# V_AUX.net
KiCad netlist of a schematic drawn in Altium Designer
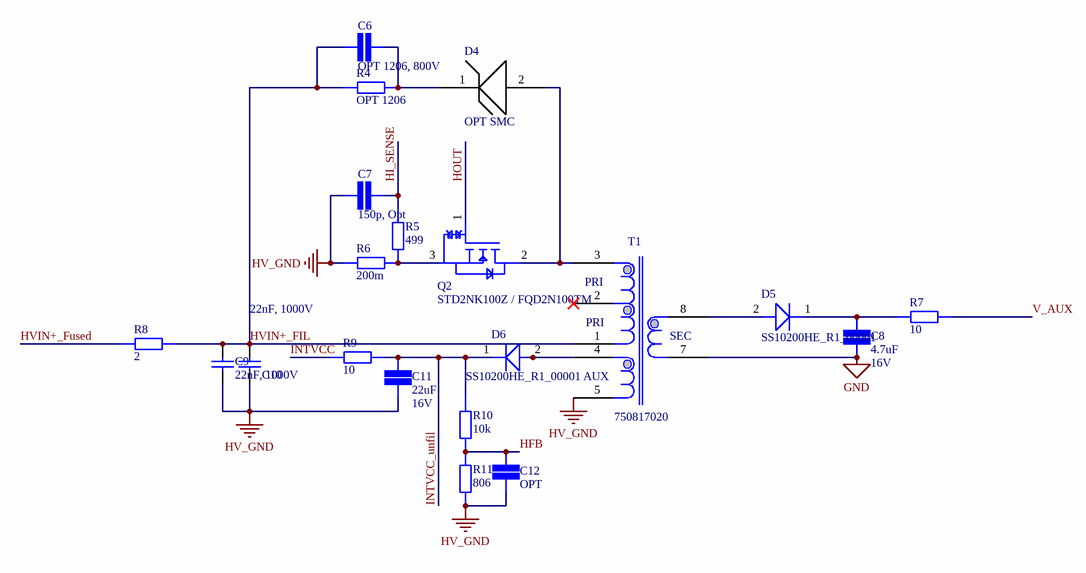
[diagram p0: V_AUX.SchDoc]

(export (version "E")
  (design (tool "Eeschema 10.0.6"))
  (components
    (comp (ref "C6")
      (value "OPT 1206, 800V")
      (footprint "CAP 1206/3216")
      (description "Capacitor with multiple Footprints")
      (fields (field (name "Comment") "SMD Capacitor"))
      (libsource (lib "") (part "SMD Capacitor_1"))
    )
    (comp (ref "C7")
      (value "150p, Opt")
      (footprint "CAP 0603/1608")
      (description "Capacitor with multiple Footprints")
      (fields (field (name "Comment") "SMD Capacitor"))
      (libsource (lib "") (part "SMD Capacitor_1"))
    )
    (comp (ref "C8")
      (value "4.7uF")
      (footprint "CAP 0603/1608")
      (description "Capacitor with multiple Footprints")
      (fields (field (name "VOLTAGE") "16V") (field (name "Comment") "SMD Capacitor"))
      (libsource (lib "Standardbauteile") (part "SMD Capacitor"))
    )
    (comp (ref "C9")
      (value "22nF, 1000V")
      (footprint "WCAP-CSMH_1210_H1.6")
      (description "WCAP-CSMH Multilayer Ceramic Chip Capacitor, size 1210, X7R Class II, 22nF, 1000V")
      (fields
        (field (name "MANUFACTURER PART NUMBER") "885342209007")
        (field (name "MANUFACTURER") "Wurth Elektronik")
      )
      (libsource (lib "Altium_WCAP-CSMH (rev20a)") (part "885342209007"))
    )
    (comp (ref "C10")
      (value "22nF, 1000V")
      (footprint "WCAP-CSMH_1210_H1.6")
      (description "WCAP-CSMH Multilayer Ceramic Chip Capacitor, size 1210, X7R Class II, 22nF, 1000V")
      (fields
        (field (name "MANUFACTURER PART NUMBER") "885342209007")
        (field (name "MANUFACTURER") "Wurth Elektronik")
      )
      (libsource (lib "Altium_WCAP-CSMH (rev20a)") (part "885342209007"))
    )
    (comp (ref "C11")
      (value "22uF")
      (footprint "CAP 0603/1608")
      (description "Capacitor with multiple Footprints")
      (fields (field (name "VOLTAGE") "16V") (field (name "Comment") "SMD Capacitor"))
      (libsource (lib "Standardbauteile") (part "SMD Capacitor"))
    )
    (comp (ref "C12")
      (value "OPT")
      (footprint "CAP 0603/1608")
      (description "Capacitor with multiple Footprints")
      (fields (field (name "Comment") "SMD Capacitor"))
      (libsource (lib "") (part "SMD Capacitor_2"))
    )
    (comp (ref "D4")
      (value "OPT SMC")
      (footprint "JEDEC DO-214AB")
      (fields
        (field (name "MANUFACTURER") "STMicroelectronics")
        (field (name "MANUFACTURER PART NUMBER") "SMC30J24A")
      )
      (libsource (lib "Integrated_LibraryLukas") (part "SMC30J24A"))
    )
    (comp (ref "D5")
      (value "SS10200HE_R1_00001")
      (footprint "Chip2PinSM127P600-8N")
      (description "Schottky 1A 200V SOD-123HE")
      (fields (field (name "MANUFACTURER") "Pan Jit"))
      (libsource (lib "Integrated_LibraryLukas_New") (part "SS10200HE_R1_00001"))
    )
    (comp (ref "D6")
      (value "SS10200HE_R1_00001")
      (footprint "Chip2PinSM127P600-8N")
      (description "Schottky 1A 200V SOD-123HE")
      (fields (field (name "MANUFACTURER") "Pan Jit"))
      (libsource (lib "Integrated_LibraryLukas_New") (part "SS10200HE_R1_00001"))
    )
    (comp (ref "Q2")
      (value "STD2NK100Z / FQD2N100TM")
      (footprint "DPAK TO-252")
      (description "N-channel 1000 V, 6.25 Ohm typ., 1.85 A, Zener-protected SuperMESH Power MOSFET in DPAK package")
      (fields
        (field (name "MANUFACTURER") "STMicroelectronics")
        (field (name "MANUFACTURER PART NUMBER") "STD2NK100Z")
      )
      (libsource (lib "Integrated_LibraryLukas_New") (part "STD2NK100Z"))
    )
    (comp (ref "R4")
      (value "OPT 1206")
      (footprint "STACKPOLE CSR1206")
      (description "Resistor with multiple footprints")
      (fields (field (name "Comment") "SMD Resistor"))
      (libsource (lib "Standardbauteile") (part "SMD Resistor"))
    )
    (comp (ref "R5")
      (value "499")
      (footprint "STACKPOLE CSR0603")
      (description "Resistor with multiple footprints")
      (fields (field (name "Comment") "SMD Resistor"))
      (libsource (lib "Standardbauteile") (part "SMD Resistor"))
    )
    (comp (ref "R6")
      (value "200m")
      (footprint "STACKPOLE CSR0603")
      (description "Resistor with multiple footprints")
      (fields (field (name "Comment") "KDV12FR200ET"))
      (libsource (lib "Standardbauteile") (part "SMD Resistor"))
    )
    (comp (ref "R7")
      (value "10")
      (footprint "STACKPOLE CSR0603")
      (description "Resistor with multiple footprints")
      (fields (field (name "Comment") "SMD Resistor"))
      (libsource (lib "Standardbauteile") (part "SMD Resistor"))
    )
    (comp (ref "R8")
      (value "2")
      (footprint "STACKPOLE CSR0603")
      (description "Resistor with multiple footprints")
      (fields (field (name "Comment") "SMD Resistor"))
      (libsource (lib "Standardbauteile") (part "SMD Resistor"))
    )
    (comp (ref "R9")
      (value "10")
      (footprint "STACKPOLE CSR0603")
      (description "Resistor with multiple footprints")
      (fields (field (name "Comment") "SMD Resistor"))
      (libsource (lib "Standardbauteile") (part "SMD Resistor"))
    )
    (comp (ref "R10")
      (value "10k")
      (footprint "STACKPOLE CSR0603")
      (description "Resistor with multiple footprints")
      (fields (field (name "Comment") "SMD Resistor"))
      (libsource (lib "Standardbauteile") (part "SMD Resistor"))
    )
    (comp (ref "R11")
      (value "806")
      (footprint "STACKPOLE CSR0603")
      (description "Resistor with multiple footprints")
      (fields (field (name "Comment") "SMD Resistor"))
      (libsource (lib "Standardbauteile") (part "SMD Resistor"))
    )
    (comp (ref "T1")
      (value "750817020")
      (footprint "750817020 Transformer")
      (description "WE Transformer")
      (libsource (lib "Integrated_LibraryLukas_New") (part "750817020"))
    )
  )
  (nets
    (net (code "1") (name "/HFB") (class "Default")
      (node (ref "C12") (pin "1") (pinfunction "1_1") (pintype "passive"))
      (node (ref "R10") (pin "2") (pinfunction "2_2") (pintype "passive"))
      (node (ref "R11") (pin "1") (pinfunction "1_1") (pintype "passive"))
    )
    (net (code "2") (name "/HI_SENSE") (class "Default")
      (node (ref "C7") (pin "2") (pinfunction "2_2") (pintype "passive"))
      (node (ref "R5") (pin "1") (pinfunction "1_1") (pintype "passive"))
    )
    (net (code "3") (name "/HOUT") (class "Default") (node (ref "Q2") (pin "1") (pintype "passive")))
    (net (code "4") (name "/HVIN+_FIL") (class "Default")
      (node (ref "C10") (pin "2") (pinfunction "2_2") (pintype "passive"))
      (node (ref "C6") (pin "1") (pinfunction "1_1") (pintype "passive"))
      (node (ref "C9") (pin "2") (pinfunction "2_2") (pintype "passive"))
      (node (ref "R4") (pin "1") (pinfunction "1_1") (pintype "passive"))
      (node (ref "R8") (pin "1") (pinfunction "1_1") (pintype "passive"))
      (node (ref "T1") (pin "1") (pintype "passive"))
    )
    (net (code "5") (name "/HVIN+_Fused") (class "Default")
      (node (ref "R8") (pin "2") (pinfunction "2_2") (pintype "passive"))
    )
    (net (code "6") (name "/INTVCC") (class "Default")
      (node (ref "R9") (pin "2") (pinfunction "2_2") (pintype "passive"))
    )
    (net (code "7") (name "/INTVCC_unfil") (class "Default")
      (node (ref "C11") (pin "2") (pinfunction "2_2") (pintype "passive"))
      (node (ref "D6") (pin "1") (pintype "passive"))
      (node (ref "R10") (pin "1") (pinfunction "1_1") (pintype "passive"))
      (node (ref "R9") (pin "1") (pinfunction "1_1") (pintype "passive"))
    )
    (net (code "8") (name "/V_AUX") (class "Default")
      (node (ref "R7") (pin "1") (pinfunction "1_1") (pintype "passive"))
    )
    (net (code "9") (name "GND") (class "Default")
      (node (ref "C8") (pin "1") (pinfunction "1_1") (pintype "passive"))
      (node (ref "T1") (pin "7") (pintype "passive"))
    )
    (net (code "10") (name "HV_GND") (class "Default")
      (node (ref "C10") (pin "1") (pinfunction "1_1") (pintype "passive"))
      (node (ref "C11") (pin "1") (pinfunction "1_1") (pintype "passive"))
      (node (ref "C12") (pin "2") (pinfunction "2_2") (pintype "passive"))
      (node (ref "C7") (pin "1") (pinfunction "1_1") (pintype "passive"))
      (node (ref "C9") (pin "1") (pinfunction "1_1") (pintype "passive"))
      (node (ref "R11") (pin "2") (pinfunction "2_2") (pintype "passive"))
      (node (ref "R6") (pin "2") (pinfunction "2_2") (pintype "passive"))
      (node (ref "T1") (pin "5") (pintype "passive"))
    )
    (net (code "11") (name "Net-(C6-Pad2)") (class "Default")
      (node (ref "C6") (pin "2") (pinfunction "2_2") (pintype "passive"))
      (node (ref "D4") (pin "1") (pintype "passive"))
      (node (ref "R4") (pin "2") (pinfunction "2_2") (pintype "passive"))
    )
    (net (code "12") (name "Net-(C8-Pad2)") (class "Default")
      (node (ref "C8") (pin "2") (pinfunction "2_2") (pintype "passive"))
      (node (ref "D5") (pin "1") (pintype "passive"))
      (node (ref "R7") (pin "2") (pinfunction "2_2") (pintype "passive"))
    )
    (net (code "13") (name "Net-(D4-Pad2)") (class "Default")
      (node (ref "D4") (pin "2") (pintype "passive"))
      (node (ref "Q2") (pin "2") (pintype "passive"))
      (node (ref "T1") (pin "3") (pintype "passive"))
    )
    (net (code "14") (name "Net-(D5-Pad2)") (class "Default")
      (node (ref "D5") (pin "2") (pintype "passive"))
      (node (ref "T1") (pin "8") (pintype "passive"))
    )
    (net (code "15") (name "Net-(D6-Pad2)") (class "Default")
      (node (ref "D6") (pin "2") (pintype "passive"))
      (node (ref "T1") (pin "4") (pintype "passive"))
    )
    (net (code "16") (name "Net-(Q2-Pad3)") (class "Default")
      (node (ref "Q2") (pin "3") (pintype "passive"))
      (node (ref "R5") (pin "2") (pinfunction "2_2") (pintype "passive"))
      (node (ref "R6") (pin "1") (pinfunction "1_1") (pintype "passive"))
    )
    (net (code "17") (name "unconnected-(T1-Pad2)") (class "Default")
      (node (ref "T1") (pin "2") (pintype "passive+no_connect"))
    )
  )
)
